# power.net
KiCad netlist of a schematic drawn in Altium Designer
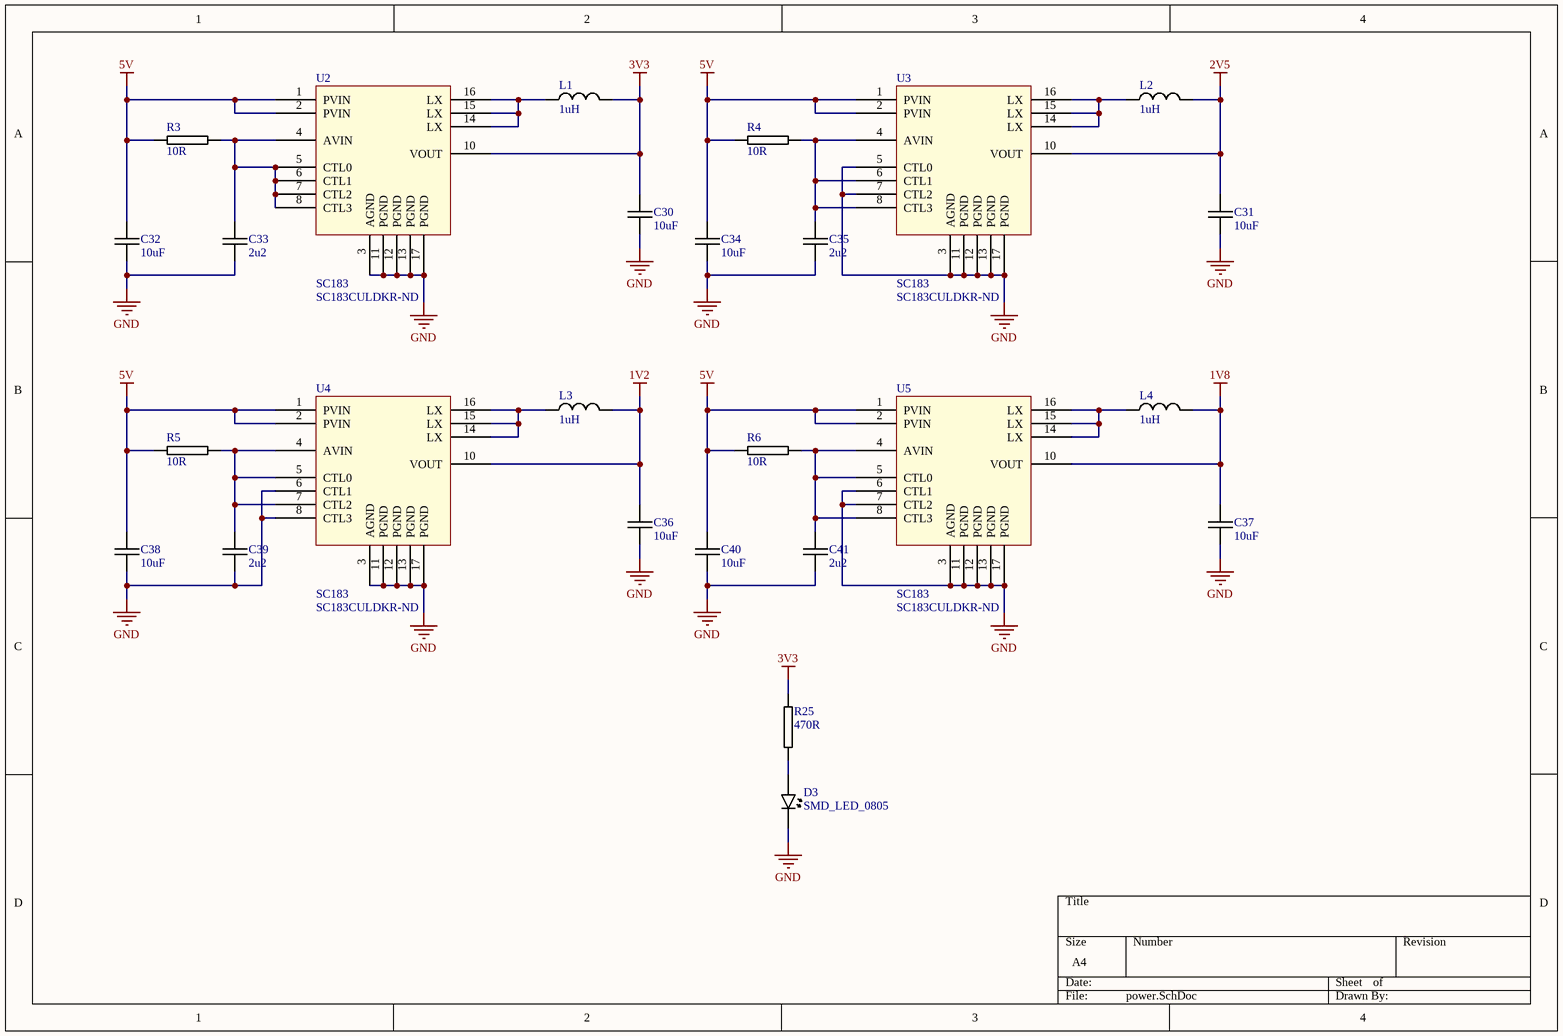
[diagram p0: power.SchDoc]

(export (version "E")
  (design (tool "Eeschema 10.0.6"))
  (components
    (comp (ref "C30")
      (value "10uF")
      (footprint "0805C-GENERIC")
      (description "CAPACITOR 0805 CERAMIC")
      (fields
        (field (name "MANUFACTURER PART NUMBER") "C2012X5R1C106M")
        (field (name "MANUFACTURER") "TDK Corporation")
      )
      (libsource (lib "vh_Altium Library") (part "0805C-10UF-16V-X5R-TDK"))
    )
    (comp (ref "C31")
      (value "10uF")
      (footprint "0805C-GENERIC")
      (description "CAPACITOR 0805 CERAMIC")
      (fields
        (field (name "MANUFACTURER PART NUMBER") "C2012X5R1C106M")
        (field (name "MANUFACTURER") "TDK Corporation")
      )
      (libsource (lib "vh_Altium Library") (part "0805C-10UF-16V-X5R-TDK"))
    )
    (comp (ref "C32")
      (value "10uF")
      (footprint "0805C-GENERIC")
      (description "CAPACITOR 0805 CERAMIC")
      (fields
        (field (name "MANUFACTURER PART NUMBER") "C2012X5R1C106M")
        (field (name "MANUFACTURER") "TDK Corporation")
      )
      (libsource (lib "vh_Altium Library") (part "0805C-10UF-16V-X5R-TDK"))
    )
    (comp (ref "C33")
      (value "2u2")
      (footprint "0805C-GENERIC")
      (description "CAPACITOR 0805 CERAMIC")
      (fields
        (field (name "MANUFACTURER PART NUMBER") "ECJ-1VB0J225K")
        (field (name "MANUFACTURER") "Panasonic - ECG")
      )
      (libsource (lib "vh_Altium Library") (part "0805C-2U2-6V3-X5R-PAN"))
    )
    (comp (ref "C34")
      (value "10uF")
      (footprint "0805C-GENERIC")
      (description "CAPACITOR 0805 CERAMIC")
      (fields
        (field (name "MANUFACTURER PART NUMBER") "C2012X5R1C106M")
        (field (name "MANUFACTURER") "TDK Corporation")
      )
      (libsource (lib "vh_Altium Library") (part "0805C-10UF-16V-X5R-TDK"))
    )
    (comp (ref "C35")
      (value "2u2")
      (footprint "0805C-GENERIC")
      (description "CAPACITOR 0805 CERAMIC")
      (fields
        (field (name "MANUFACTURER PART NUMBER") "ECJ-1VB0J225K")
        (field (name "MANUFACTURER") "Panasonic - ECG")
      )
      (libsource (lib "vh_Altium Library") (part "0805C-2U2-6V3-X5R-PAN"))
    )
    (comp (ref "C36")
      (value "10uF")
      (footprint "0805C-GENERIC")
      (description "CAPACITOR 0805 CERAMIC")
      (fields
        (field (name "MANUFACTURER PART NUMBER") "C2012X5R1C106M")
        (field (name "MANUFACTURER") "TDK Corporation")
      )
      (libsource (lib "vh_Altium Library") (part "0805C-10UF-16V-X5R-TDK"))
    )
    (comp (ref "C37")
      (value "10uF")
      (footprint "0805C-GENERIC")
      (description "CAPACITOR 0805 CERAMIC")
      (fields
        (field (name "MANUFACTURER PART NUMBER") "C2012X5R1C106M")
        (field (name "MANUFACTURER") "TDK Corporation")
      )
      (libsource (lib "vh_Altium Library") (part "0805C-10UF-16V-X5R-TDK"))
    )
    (comp (ref "C38")
      (value "10uF")
      (footprint "0805C-GENERIC")
      (description "CAPACITOR 0805 CERAMIC")
      (fields
        (field (name "MANUFACTURER PART NUMBER") "C2012X5R1C106M")
        (field (name "MANUFACTURER") "TDK Corporation")
      )
      (libsource (lib "vh_Altium Library") (part "0805C-10UF-16V-X5R-TDK"))
    )
    (comp (ref "C39")
      (value "2u2")
      (footprint "0805C-GENERIC")
      (description "CAPACITOR 0805 CERAMIC")
      (fields
        (field (name "MANUFACTURER PART NUMBER") "ECJ-1VB0J225K")
        (field (name "MANUFACTURER") "Panasonic - ECG")
      )
      (libsource (lib "vh_Altium Library") (part "0805C-2U2-6V3-X5R-PAN"))
    )
    (comp (ref "C40")
      (value "10uF")
      (footprint "0805C-GENERIC")
      (description "CAPACITOR 0805 CERAMIC")
      (fields
        (field (name "MANUFACTURER PART NUMBER") "C2012X5R1C106M")
        (field (name "MANUFACTURER") "TDK Corporation")
      )
      (libsource (lib "vh_Altium Library") (part "0805C-10UF-16V-X5R-TDK"))
    )
    (comp (ref "C41")
      (value "2u2")
      (footprint "0805C-GENERIC")
      (description "CAPACITOR 0805 CERAMIC")
      (fields
        (field (name "MANUFACTURER PART NUMBER") "ECJ-1VB0J225K")
        (field (name "MANUFACTURER") "Panasonic - ECG")
      )
      (libsource (lib "vh_Altium Library") (part "0805C-2U2-6V3-X5R-PAN"))
    )
    (comp (ref "D3")
      (value "SMD_LED_0805")
      (footprint "CD2012-0805")
      (libsource (lib "camera_board") (part "SMD_LED_0805"))
    )
    (comp (ref "L1")
      (value "1uH")
      (footprint "VISHAY-IHLP1616-GENERIC")
      (description "INDUCTOR POWER 1.0UH 4.0A SMD")
      (fields (field (name "MANUFACTURER PART NUMBER") "IHLP1616ABER1R0M01"))
      (libsource (lib "vh_Altium Library") (part "1U-IHLP1616-VISHAY"))
    )
    (comp (ref "L2")
      (value "1uH")
      (footprint "VISHAY-IHLP1616-GENERIC")
      (description "INDUCTOR POWER 1.0UH 4.0A SMD")
      (fields (field (name "MANUFACTURER PART NUMBER") "IHLP1616ABER1R0M01"))
      (libsource (lib "vh_Altium Library") (part "1U-IHLP1616-VISHAY"))
    )
    (comp (ref "L3")
      (value "1uH")
      (footprint "VISHAY-IHLP1616-GENERIC")
      (description "INDUCTOR POWER 1.0UH 4.0A SMD")
      (fields (field (name "MANUFACTURER PART NUMBER") "IHLP1616ABER1R0M01"))
      (libsource (lib "vh_Altium Library") (part "1U-IHLP1616-VISHAY"))
    )
    (comp (ref "L4")
      (value "1uH")
      (footprint "VISHAY-IHLP1616-GENERIC")
      (description "INDUCTOR POWER 1.0UH 4.0A SMD")
      (fields (field (name "MANUFACTURER PART NUMBER") "IHLP1616ABER1R0M01"))
      (libsource (lib "vh_Altium Library") (part "1U-IHLP1616-VISHAY"))
    )
    (comp (ref "R3")
      (value "10R")
      (footprint "0603R-10")
      (description "GENERIC RESISTOR 0603")
      (fields
        (field (name "MANUFACTURER PART NUMBER") "RMCF 1/16 10 1% R")
        (field (name "MANUFACTURER") "Stackpole Electronics Inc")
      )
      (libsource (lib "vh_Altium Library") (part "0603R-10R"))
    )
    (comp (ref "R4")
      (value "10R")
      (footprint "0603R-10")
      (description "GENERIC RESISTOR 0603")
      (fields
        (field (name "MANUFACTURER PART NUMBER") "RMCF 1/16 10 1% R")
        (field (name "MANUFACTURER") "Stackpole Electronics Inc")
      )
      (libsource (lib "vh_Altium Library") (part "0603R-10R"))
    )
    (comp (ref "R5")
      (value "10R")
      (footprint "0603R-10")
      (description "GENERIC RESISTOR 0603")
      (fields
        (field (name "MANUFACTURER PART NUMBER") "RMCF 1/16 10 1% R")
        (field (name "MANUFACTURER") "Stackpole Electronics Inc")
      )
      (libsource (lib "vh_Altium Library") (part "0603R-10R"))
    )
    (comp (ref "R6")
      (value "10R")
      (footprint "0603R-10")
      (description "GENERIC RESISTOR 0603")
      (fields
        (field (name "MANUFACTURER PART NUMBER") "RMCF 1/16 10 1% R")
        (field (name "MANUFACTURER") "Stackpole Electronics Inc")
      )
      (libsource (lib "vh_Altium Library") (part "0603R-10R"))
    )
    (comp (ref "R25")
      (value "470R")
      (footprint "0603R-470")
      (description "GENERIC RESISTOR 0603")
      (fields (field (name "MANUFACTURER PART NUMBER") "RMCF 1/16 470 1% R") (field (name "TOLERANCE") "±1%"))
      (libsource (lib "vh_Altium Library") (part "0603R-470"))
    )
    (comp (ref "U2")
      (value "SC183")
      (footprint "QFN50P300X300-16V6N")
      (fields (field (name "SUPPLIER PART NUMBER 1") "SC183CULDKR-ND"))
      (libsource (lib "DIPFPGA") (part "SC183"))
    )
    (comp (ref "U3")
      (value "SC183")
      (footprint "QFN50P300X300-16V6N")
      (fields (field (name "SUPPLIER PART NUMBER 1") "SC183CULDKR-ND"))
      (libsource (lib "DIPFPGA") (part "SC183"))
    )
    (comp (ref "U4")
      (value "SC183")
      (footprint "QFN50P300X300-16V6N")
      (fields (field (name "SUPPLIER PART NUMBER 1") "SC183CULDKR-ND"))
      (libsource (lib "DIPFPGA") (part "SC183"))
    )
    (comp (ref "U5")
      (value "SC183")
      (footprint "QFN50P300X300-16V6N")
      (fields (field (name "SUPPLIER PART NUMBER 1") "SC183CULDKR-ND"))
      (libsource (lib "DIPFPGA") (part "SC183"))
    )
  )
  (nets
    (net (code "1") (name "1V2") (class "Default")
      (node (ref "C36") (pin "1") (pintype "passive"))
      (node (ref "L3") (pin "2") (pinfunction "2_2") (pintype "passive"))
      (node (ref "U4") (pin "10") (pinfunction "VOUT_10") (pintype "passive"))
    )
    (net (code "2") (name "1V8") (class "Default")
      (node (ref "C37") (pin "1") (pintype "passive"))
      (node (ref "L4") (pin "2") (pinfunction "2_2") (pintype "passive"))
      (node (ref "U5") (pin "10") (pinfunction "VOUT_10") (pintype "passive"))
    )
    (net (code "3") (name "2V5") (class "Default")
      (node (ref "C31") (pin "1") (pintype "passive"))
      (node (ref "L2") (pin "2") (pinfunction "2_2") (pintype "passive"))
      (node (ref "U3") (pin "10") (pinfunction "VOUT_10") (pintype "passive"))
    )
    (net (code "4") (name "3V3") (class "Default")
      (node (ref "C30") (pin "1") (pintype "passive"))
      (node (ref "L1") (pin "2") (pinfunction "2_2") (pintype "passive"))
      (node (ref "R25") (pin "1") (pintype "passive"))
      (node (ref "U2") (pin "10") (pinfunction "VOUT_10") (pintype "passive"))
    )
    (net (code "5") (name "5V") (class "Default")
      (node (ref "C32") (pin "1") (pintype "passive"))
      (node (ref "C34") (pin "1") (pintype "passive"))
      (node (ref "C38") (pin "1") (pintype "passive"))
      (node (ref "C40") (pin "1") (pintype "passive"))
      (node (ref "R3") (pin "1") (pintype "passive"))
      (node (ref "R4") (pin "1") (pintype "passive"))
      (node (ref "R5") (pin "1") (pintype "passive"))
      (node (ref "R6") (pin "1") (pintype "passive"))
      (node (ref "U2") (pin "1") (pinfunction "PVIN_1") (pintype "passive"))
      (node (ref "U2") (pin "2") (pinfunction "PVIN_2") (pintype "passive"))
      (node (ref "U3") (pin "1") (pinfunction "PVIN_1") (pintype "passive"))
      (node (ref "U3") (pin "2") (pinfunction "PVIN_2") (pintype "passive"))
      (node (ref "U4") (pin "1") (pinfunction "PVIN_1") (pintype "passive"))
      (node (ref "U4") (pin "2") (pinfunction "PVIN_2") (pintype "passive"))
      (node (ref "U5") (pin "1") (pinfunction "PVIN_1") (pintype "passive"))
      (node (ref "U5") (pin "2") (pinfunction "PVIN_2") (pintype "passive"))
    )
    (net (code "6") (name "GND") (class "Default")
      (node (ref "C30") (pin "2") (pintype "passive"))
      (node (ref "C31") (pin "2") (pintype "passive"))
      (node (ref "C32") (pin "2") (pintype "passive"))
      (node (ref "C33") (pin "2") (pintype "passive"))
      (node (ref "C34") (pin "2") (pintype "passive"))
      (node (ref "C35") (pin "2") (pintype "passive"))
      (node (ref "C36") (pin "2") (pintype "passive"))
      (node (ref "C37") (pin "2") (pintype "passive"))
      (node (ref "C38") (pin "2") (pintype "passive"))
      (node (ref "C39") (pin "2") (pintype "passive"))
      (node (ref "C40") (pin "2") (pintype "passive"))
      (node (ref "C41") (pin "2") (pintype "passive"))
      (node (ref "D3") (pin "2") (pinfunction "K_2") (pintype "passive"))
      (node (ref "U2") (pin "11") (pinfunction "PGND_11") (pintype "passive"))
      (node (ref "U2") (pin "12") (pinfunction "PGND_12") (pintype "passive"))
      (node (ref "U2") (pin "13") (pinfunction "PGND_13") (pintype "passive"))
      (node (ref "U2") (pin "17") (pinfunction "PGND_17") (pintype "passive"))
      (node (ref "U2") (pin "3") (pinfunction "AGND_3") (pintype "passive"))
      (node (ref "U3") (pin "11") (pinfunction "PGND_11") (pintype "passive"))
      (node (ref "U3") (pin "12") (pinfunction "PGND_12") (pintype "passive"))
      (node (ref "U3") (pin "13") (pinfunction "PGND_13") (pintype "passive"))
      (node (ref "U3") (pin "17") (pinfunction "PGND_17") (pintype "passive"))
      (node (ref "U3") (pin "3") (pinfunction "AGND_3") (pintype "passive"))
      (node (ref "U3") (pin "5") (pinfunction "CTL0_5") (pintype "passive"))
      (node (ref "U3") (pin "7") (pinfunction "CTL2_7") (pintype "passive"))
      (node (ref "U4") (pin "11") (pinfunction "PGND_11") (pintype "passive"))
      (node (ref "U4") (pin "12") (pinfunction "PGND_12") (pintype "passive"))
      (node (ref "U4") (pin "13") (pinfunction "PGND_13") (pintype "passive"))
      (node (ref "U4") (pin "17") (pinfunction "PGND_17") (pintype "passive"))
      (node (ref "U4") (pin "3") (pinfunction "AGND_3") (pintype "passive"))
      (node (ref "U4") (pin "6") (pinfunction "CTL1_6") (pintype "passive"))
      (node (ref "U4") (pin "8") (pinfunction "CTL3_8") (pintype "passive"))
      (node (ref "U5") (pin "11") (pinfunction "PGND_11") (pintype "passive"))
      (node (ref "U5") (pin "12") (pinfunction "PGND_12") (pintype "passive"))
      (node (ref "U5") (pin "13") (pinfunction "PGND_13") (pintype "passive"))
      (node (ref "U5") (pin "17") (pinfunction "PGND_17") (pintype "passive"))
      (node (ref "U5") (pin "3") (pinfunction "AGND_3") (pintype "passive"))
      (node (ref "U5") (pin "6") (pinfunction "CTL1_6") (pintype "passive"))
      (node (ref "U5") (pin "7") (pinfunction "CTL2_7") (pintype "passive"))
    )
    (net (code "7") (name "Net-(D3-A)") (class "Default")
      (node (ref "D3") (pin "1") (pinfunction "A_1") (pintype "passive"))
      (node (ref "R25") (pin "2") (pintype "passive"))
    )
    (net (code "8") (name "Net-(L1-Pad1)") (class "Default")
      (node (ref "L1") (pin "1") (pinfunction "1_1") (pintype "passive"))
      (node (ref "U2") (pin "14") (pinfunction "LX_14") (pintype "passive"))
      (node (ref "U2") (pin "15") (pinfunction "LX_15") (pintype "passive"))
      (node (ref "U2") (pin "16") (pinfunction "LX_16") (pintype "passive"))
    )
    (net (code "9") (name "Net-(L2-Pad1)") (class "Default")
      (node (ref "L2") (pin "1") (pinfunction "1_1") (pintype "passive"))
      (node (ref "U3") (pin "14") (pinfunction "LX_14") (pintype "passive"))
      (node (ref "U3") (pin "15") (pinfunction "LX_15") (pintype "passive"))
      (node (ref "U3") (pin "16") (pinfunction "LX_16") (pintype "passive"))
    )
    (net (code "10") (name "Net-(L3-Pad1)") (class "Default")
      (node (ref "L3") (pin "1") (pinfunction "1_1") (pintype "passive"))
      (node (ref "U4") (pin "14") (pinfunction "LX_14") (pintype "passive"))
      (node (ref "U4") (pin "15") (pinfunction "LX_15") (pintype "passive"))
      (node (ref "U4") (pin "16") (pinfunction "LX_16") (pintype "passive"))
    )
    (net (code "11") (name "Net-(L4-Pad1)") (class "Default")
      (node (ref "L4") (pin "1") (pinfunction "1_1") (pintype "passive"))
      (node (ref "U5") (pin "14") (pinfunction "LX_14") (pintype "passive"))
      (node (ref "U5") (pin "15") (pinfunction "LX_15") (pintype "passive"))
      (node (ref "U5") (pin "16") (pinfunction "LX_16") (pintype "passive"))
    )
    (net (code "12") (name "Net-(U2-AVIN)") (class "Default")
      (node (ref "C33") (pin "1") (pintype "passive"))
      (node (ref "R3") (pin "2") (pintype "passive"))
      (node (ref "U2") (pin "4") (pinfunction "AVIN_4") (pintype "passive"))
      (node (ref "U2") (pin "5") (pinfunction "CTL0_5") (pintype "passive"))
      (node (ref "U2") (pin "6") (pinfunction "CTL1_6") (pintype "passive"))
      (node (ref "U2") (pin "7") (pinfunction "CTL2_7") (pintype "passive"))
      (node (ref "U2") (pin "8") (pinfunction "CTL3_8") (pintype "passive"))
    )
    (net (code "13") (name "Net-(U3-AVIN)") (class "Default")
      (node (ref "C35") (pin "1") (pintype "passive"))
      (node (ref "R4") (pin "2") (pintype "passive"))
      (node (ref "U3") (pin "4") (pinfunction "AVIN_4") (pintype "passive"))
      (node (ref "U3") (pin "6") (pinfunction "CTL1_6") (pintype "passive"))
      (node (ref "U3") (pin "8") (pinfunction "CTL3_8") (pintype "passive"))
    )
    (net (code "14") (name "Net-(U4-AVIN)") (class "Default")
      (node (ref "C39") (pin "1") (pintype "passive"))
      (node (ref "R5") (pin "2") (pintype "passive"))
      (node (ref "U4") (pin "4") (pinfunction "AVIN_4") (pintype "passive"))
      (node (ref "U4") (pin "5") (pinfunction "CTL0_5") (pintype "passive"))
      (node (ref "U4") (pin "7") (pinfunction "CTL2_7") (pintype "passive"))
    )
    (net (code "15") (name "Net-(U5-AVIN)") (class "Default")
      (node (ref "C41") (pin "1") (pintype "passive"))
      (node (ref "R6") (pin "2") (pintype "passive"))
      (node (ref "U5") (pin "4") (pinfunction "AVIN_4") (pintype "passive"))
      (node (ref "U5") (pin "5") (pinfunction "CTL0_5") (pintype "passive"))
      (node (ref "U5") (pin "8") (pinfunction "CTL3_8") (pintype "passive"))
    )
  )
)
